# Key.net
KiCad netlist of a schematic drawn in Altium Designer
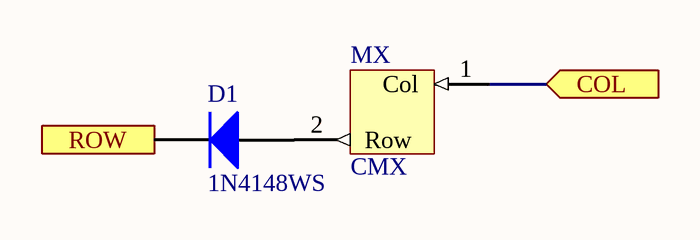
[diagram p0: Key.SchDoc]

(export (version "E")
  (design (tool "Eeschema 10.0.6"))
  (components
    (comp (ref "D1")
      (value "1N4148WS")
      (footprint "DIOD-SOD323-2-A_V")
      (description "Fast Switching Diode, 75 V, 0.3 A, -65 to 150 degC, 2-Pin SOD323, RoHS, Tape and Reel")
      (libsource (lib "Altium Content Vault") (part "D-AK-2"))
    )
    (comp (ref "MX")
      (value "CMX")
      (footprint "MX")
      (description "Cherry MX Footprint")
      (libsource (lib "Skayboard") (part "MX"))
    )
  )
  (nets
    (net (code "1") (name "/COL") (class "Default")
      (node (ref "MX") (pin "1") (pinfunction "Col_1") (pintype "input"))
    )
    (net (code "2") (name "/ROW") (class "Default")
      (node (ref "D1") (pin "2") (pinfunction "K_2") (pintype "passive"))
    )
    (net (code "3") (name "Net-(D1-A)") (class "Default")
      (node (ref "D1") (pin "1") (pinfunction "A_1") (pintype "passive"))
      (node (ref "MX") (pin "2") (pinfunction "Row_2") (pintype "output"))
    )
  )
)
